# Drehzahlregler-Einfach.net
KiCad netlist of a schematic drawn in EAGLE
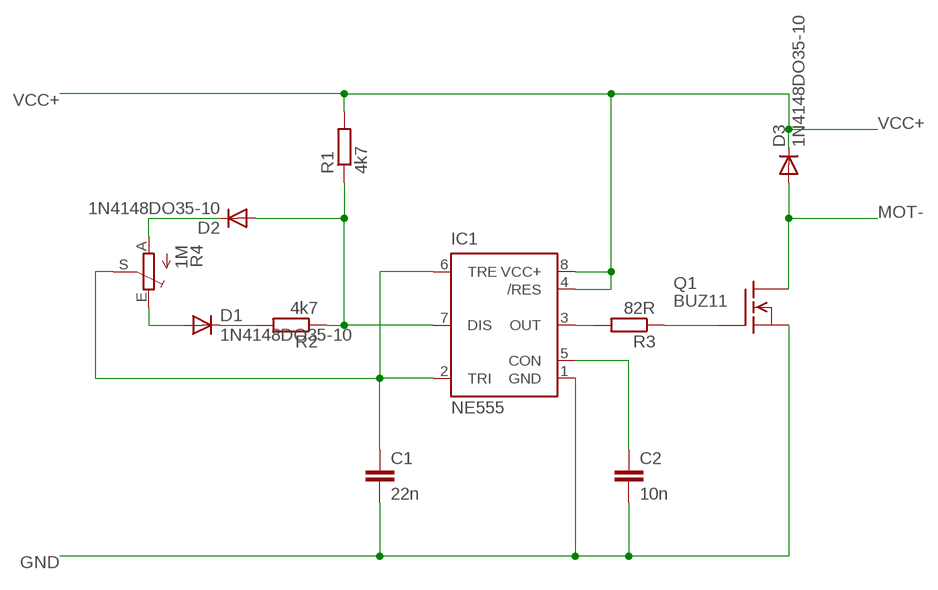
[diagram p0: schematic, sheet 1]

(export (version "E")
  (design (tool "Eeschema 10.0.6"))
  (components
    (comp (ref "C1")
      (value "22n")
      (footprint "eagle-import:C5B2.5")
      (libsource (lib "eagle-import") (part "C5/2.5"))
    )
    (comp (ref "C2")
      (value "10n")
      (footprint "eagle-import:C5B2.5")
      (libsource (lib "eagle-import") (part "C5/2.5"))
    )
    (comp (ref "D1")
      (value "1N4148DO35-10")
      (footprint "eagle-import:DO35-10")
      (libsource (lib "eagle-import") (part "1N4148DO35-10"))
    )
    (comp (ref "D2")
      (value "1N4148DO35-10")
      (footprint "eagle-import:DO35-10")
      (libsource (lib "eagle-import") (part "1N4148DO35-10"))
    )
    (comp (ref "D3")
      (value "1N4148DO35-10")
      (footprint "eagle-import:DO35-10")
      (libsource (lib "eagle-import") (part "1N4148DO35-10"))
    )
    (comp (ref "IC1")
      (value "NE555")
      (footprint "eagle-import:DIL-08")
      (fields (field (name "MF") "Arrow Electronics") (field (name "MPN") "NE555N"))
      (libsource (lib "eagle-import") (part "NE555"))
    )
    (comp (ref "Q1")
      (value "BUZ11")
      (footprint "eagle-import:TO220")
      (libsource (lib "eagle-import") (part "BUZ11"))
    )
    (comp (ref "R1")
      (value "4k7")
      (footprint "eagle-import:0207_10")
      (libsource (lib "eagle-import") (part "R-EU_0207/10"))
    )
    (comp (ref "R2")
      (value "4k7")
      (footprint "eagle-import:0207_10")
      (libsource (lib "eagle-import") (part "R-EU_0207/10"))
    )
    (comp (ref "R3")
      (value "82R")
      (footprint "eagle-import:0207_10")
      (libsource (lib "eagle-import") (part "R-EU_0207/10"))
    )
    (comp (ref "R4")
      (value "1M")
      (footprint "eagle-import:CIP20C-4MM")
      (libsource (lib "eagle-import") (part "TRIM_EU-CIP20C-4MM"))
    )
  )
  (nets
    (net (code "1") (name "/GND") (class "Default")
      (node (ref "C1") (pin "2") (pinfunction "2_2") (pintype "passive"))
      (node (ref "C2") (pin "2") (pinfunction "2_2") (pintype "passive"))
      (node (ref "IC1") (pin "1") (pinfunction "GND_1") (pintype "power_in"))
      (node (ref "Q1") (pin "3") (pinfunction "S_3") (pintype "passive"))
    )
    (net (code "2") (name "/MOT-") (class "Default")
      (node (ref "D3") (pin "A") (pinfunction "A_A") (pintype "passive"))
      (node (ref "Q1") (pin "2") (pinfunction "D_2") (pintype "passive"))
    )
    (net (code "3") (name "/VCC+") (class "Default")
      (node (ref "D3") (pin "C") (pinfunction "C_C") (pintype "passive"))
      (node (ref "IC1") (pin "4") (pinfunction "/RES_4") (pintype "input"))
      (node (ref "IC1") (pin "8") (pinfunction "VCC+_8") (pintype "power_in"))
      (node (ref "R1") (pin "2") (pinfunction "2_2") (pintype "passive"))
    )
    (net (code "4") (name "Net-(D1-PadA)") (class "Default")
      (node (ref "D1") (pin "A") (pinfunction "A_A") (pintype "passive"))
      (node (ref "R4") (pin "E") (pinfunction "E_E") (pintype "passive"))
    )
    (net (code "5") (name "Net-(D1-PadC)") (class "Default")
      (node (ref "D1") (pin "C") (pinfunction "C_C") (pintype "passive"))
      (node (ref "R2") (pin "2") (pinfunction "2_2") (pintype "passive"))
    )
    (net (code "6") (name "Net-(D2-PadC)") (class "Default")
      (node (ref "D2") (pin "C") (pinfunction "C_C") (pintype "passive"))
      (node (ref "R4") (pin "A") (pinfunction "A_A") (pintype "passive"))
    )
    (net (code "7") (name "Net-(IC1-CON)") (class "Default")
      (node (ref "C2") (pin "1") (pinfunction "1_1") (pintype "passive"))
      (node (ref "IC1") (pin "5") (pinfunction "CON_5") (pintype "input"))
    )
    (net (code "8") (name "Net-(IC1-DIS)") (class "Default")
      (node (ref "D2") (pin "A") (pinfunction "A_A") (pintype "passive"))
      (node (ref "IC1") (pin "7") (pinfunction "DIS_7") (pintype "input"))
      (node (ref "R1") (pin "1") (pinfunction "1_1") (pintype "passive"))
      (node (ref "R2") (pin "1") (pinfunction "1_1") (pintype "passive"))
    )
    (net (code "9") (name "Net-(IC1-OUT)") (class "Default")
      (node (ref "IC1") (pin "3") (pinfunction "OUT_3") (pintype "output"))
      (node (ref "R3") (pin "2") (pinfunction "2_2") (pintype "passive"))
    )
    (net (code "10") (name "Net-(IC1-TRE)") (class "Default")
      (node (ref "C1") (pin "1") (pinfunction "1_1") (pintype "passive"))
      (node (ref "IC1") (pin "2") (pinfunction "TRI_2") (pintype "input"))
      (node (ref "IC1") (pin "6") (pinfunction "TRE_6") (pintype "input"))
      (node (ref "R4") (pin "S") (pinfunction "S_S") (pintype "passive"))
    )
    (net (code "11") (name "Net-(Q1-G)") (class "Default")
      (node (ref "Q1") (pin "1") (pinfunction "G_1") (pintype "passive"))
      (node (ref "R3") (pin "1") (pinfunction "1_1") (pintype "passive"))
    )
  )
)
